# MCU_board_in_foot_v3.net
KiCad netlist of a schematic drawn in EAGLE
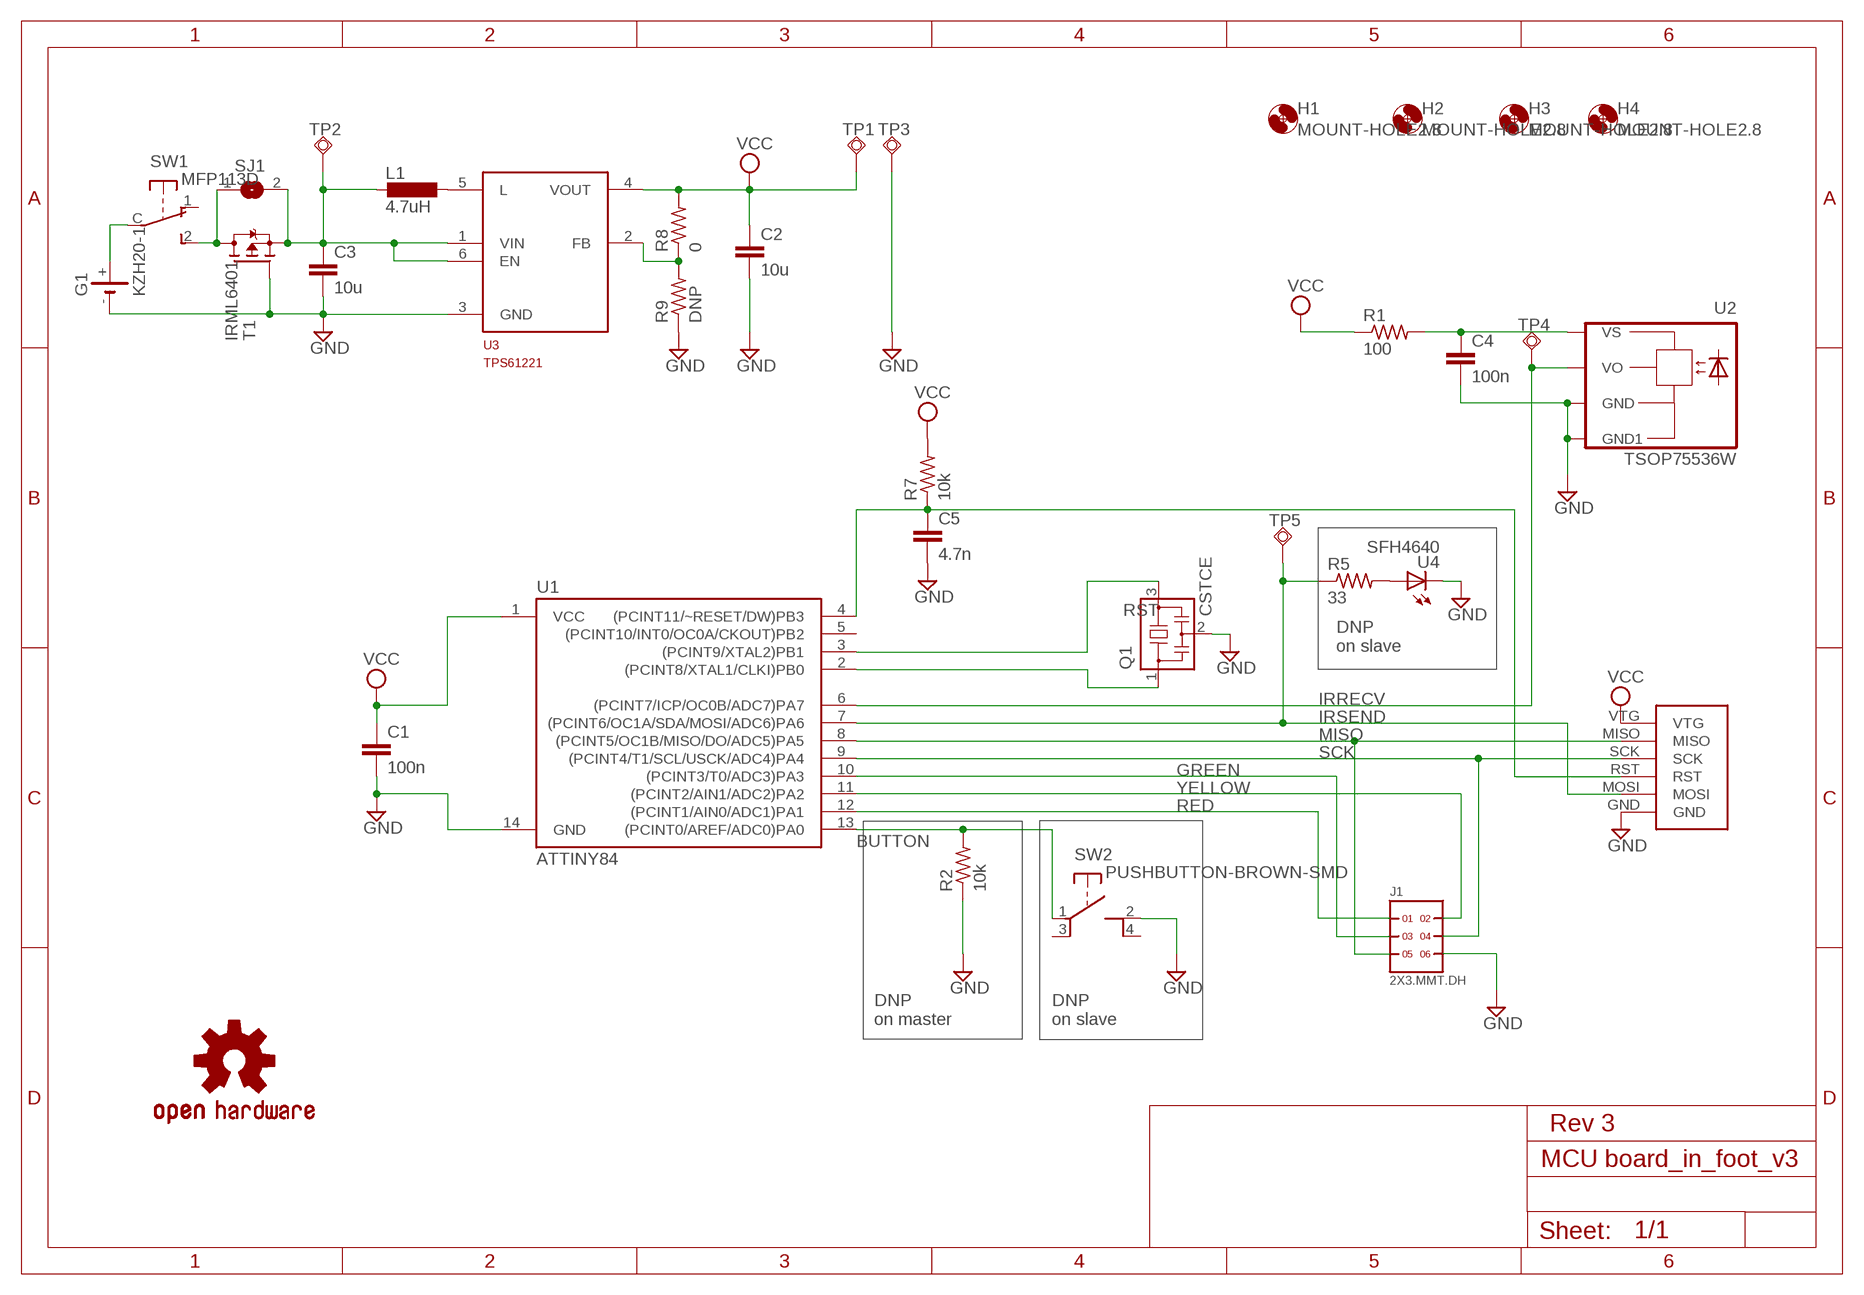
[diagram p0: schematic, sheet 1]

(export (version "E")
  (design (tool "Eeschema 10.0.6"))
  (components
    (comp (ref "C1")
      (value "100n")
      (footprint "eagle-import:0603-CAP")
      (libsource (lib "eagle-import") (part "CAP0603-CAP"))
    )
    (comp (ref "C2")
      (value "10u")
      (footprint "eagle-import:0603-CAP")
      (libsource (lib "eagle-import") (part "CAP0603-CAP"))
    )
    (comp (ref "C3")
      (value "10u")
      (footprint "eagle-import:0603-CAP")
      (libsource (lib "eagle-import") (part "MCU board_in_foot_99087_CAP0603-CAP"))
    )
    (comp (ref "C4")
      (value "100n")
      (footprint "eagle-import:0603-CAP")
      (libsource (lib "eagle-import") (part "CAP0603-CAP"))
    )
    (comp (ref "C5")
      (value "4.7n")
      (footprint "eagle-import:0603-CAP")
      (libsource (lib "eagle-import") (part "MCU board_in_foot_99087_CAP0603-CAP"))
    )
    (comp (ref "G1")
      (value "KZH20-1")
      (footprint "eagle-import:KZH20-1")
      (libsource (lib "eagle-import") (part "KZH20-1"))
    )
    (comp (ref "H1")
      (value "MOUNT-HOLE2.8")
      (footprint "eagle-import:2,8")
      (libsource (lib "eagle-import") (part "MCU board_in_foot_99087_MOUNT-HOLE2.8"))
    )
    (comp (ref "H2")
      (value "MOUNT-HOLE2.8")
      (footprint "eagle-import:2,8")
      (libsource (lib "eagle-import") (part "MOUNT-HOLE2.8"))
    )
    (comp (ref "H3")
      (value "MOUNT-HOLE2.8")
      (footprint "eagle-import:2,8")
      (libsource (lib "eagle-import") (part "MOUNT-HOLE2.8"))
    )
    (comp (ref "H4")
      (value "MOUNT-HOLE2.8")
      (footprint "eagle-import:2,8")
      (libsource (lib "eagle-import") (part "MCU board_in_foot_99087_MOUNT-HOLE2.8"))
    )
    (comp (ref "ISP")
      (value "ISP_POGOSURFACE")
      (footprint "eagle-import:ISP_SURFACE")
      (libsource (lib "eagle-import") (part "ISP_POGOSURFACE"))
    )
    (comp (ref "J1")
      (value "2X3.MMT.DH")
      (footprint "eagle-import:2X3_MMT.103.01.X.DH")
      (libsource (lib "eagle-import") (part "2X3.MMT.DH"))
    )
    (comp (ref "L1")
      (value "4.7uH")
      (footprint "eagle-import:EPL2010")
      (libsource (lib "eagle-import") (part "EPL2010"))
    )
    (comp (ref "LOGO1")
      (value "OSHW-LOGOS")
      (footprint "eagle-import:OSHW-LOGO-S")
      (libsource (lib "eagle-import") (part "OSHW-LOGOS"))
    )
    (comp (ref "Q1")
      (value "CSTCE")
      (footprint "eagle-import:CSTCE")
      (libsource (lib "eagle-import") (part "CSTCE"))
    )
    (comp (ref "R1")
      (value "100")
      (footprint "eagle-import:R0603")
      (libsource (lib "eagle-import") (part "R-US_R0603"))
    )
    (comp (ref "R2")
      (value "10k")
      (footprint "eagle-import:R0603")
      (libsource (lib "eagle-import") (part "R-US_R0603"))
    )
    (comp (ref "R5")
      (value "33")
      (footprint "eagle-import:R0603")
      (libsource (lib "eagle-import") (part "R-US_R0603"))
    )
    (comp (ref "R7")
      (value "10k")
      (footprint "eagle-import:R0603")
      (libsource (lib "eagle-import") (part "R-US_R0603"))
    )
    (comp (ref "R8")
      (value "0")
      (footprint "eagle-import:R0603")
      (libsource (lib "eagle-import") (part "R-US_R0603"))
    )
    (comp (ref "R9")
      (value "DNP")
      (footprint "eagle-import:R0603")
      (libsource (lib "eagle-import") (part "R-US_R0603"))
    )
    (comp (ref "SJ1") (value "SJ") (footprint "eagle-import:SJ") (libsource (lib "eagle-import") (part "SJ")))
    (comp (ref "SW1")
      (value "MFP113D")
      (footprint "eagle-import:MFP-SLIDER")
      (libsource (lib "eagle-import") (part "MFP113D"))
    )
    (comp (ref "SW2")
      (value "PUSHBUTTON-BROWN-SMD")
      (footprint "eagle-import:SMD-SW")
      (libsource (lib "eagle-import") (part "PUSHBUTTON-BROWN-SMD"))
    )
    (comp (ref "T1")
      (value "IRML6401")
      (footprint "eagle-import:SOT23")
      (libsource (lib "eagle-import") (part "IRML6401"))
    )
    (comp (ref "TP1")
      (value "TPSQTP20SQTH")
      (footprint "eagle-import:TP20SQTH")
      (libsource (lib "eagle-import") (part "TPSQTP20SQTH"))
    )
    (comp (ref "TP2")
      (value "TPSQTP20SQTH")
      (footprint "eagle-import:TP20SQTH")
      (libsource (lib "eagle-import") (part "TPSQTP20SQTH"))
    )
    (comp (ref "TP3")
      (value "TPSQTP20SQTH")
      (footprint "eagle-import:TP20SQTH")
      (libsource (lib "eagle-import") (part "TPSQTP20SQTH"))
    )
    (comp (ref "TP4")
      (value "TPSQTP20SQTH")
      (footprint "eagle-import:TP20SQTH")
      (libsource (lib "eagle-import") (part "TPSQTP20SQTH"))
    )
    (comp (ref "TP5")
      (value "TPSQTP20SQTH")
      (footprint "eagle-import:TP20SQTH")
      (libsource (lib "eagle-import") (part "TPSQTP20SQTH"))
    )
    (comp (ref "U1")
      (value "ATTINY84")
      (footprint "eagle-import:SO14")
      (libsource (lib "eagle-import") (part "ATTINY84"))
    )
    (comp (ref "U2")
      (value "TSOP75536W")
      (footprint "eagle-import:TSOP75W-TOPLOOK")
      (libsource (lib "eagle-import") (part "TSOP75WTOPLOOK"))
    )
    (comp (ref "U3")
      (value "TPS61221")
      (footprint "eagle-import:DCK-R_PDSO_G6")
      (libsource (lib "eagle-import") (part "TPS61220"))
    )
    (comp (ref "U4")
      (value "SFH4640")
      (footprint "eagle-import:MIDLED")
      (libsource (lib "eagle-import") (part "SFH4640"))
    )
  )
  (nets
    (net (code "1") (name "/BUTTON") (class "Default")
      (node (ref "R2") (pin "2") (pinfunction "2_2") (pintype "passive"))
      (node (ref "SW2") (pin "1") (pinfunction "P1_1") (pintype "passive"))
      (node (ref "U1") (pin "13") (pinfunction "(PCINT0/AREF/ADC0)PA0_13") (pintype "bidirectional"))
    )
    (net (code "2") (name "/GREEN") (class "Default")
      (node (ref "J1") (pin "3") (pinfunction "3_3") (pintype "bidirectional"))
      (node (ref "U1") (pin "10") (pinfunction "(PCINT3/T0/ADC3)PA3_10") (pintype "bidirectional"))
    )
    (net (code "3") (name "/IRRECV") (class "Default")
      (node (ref "TP4") (pin "TP") (pinfunction "TP_TP") (pintype "input"))
      (node (ref "U1") (pin "6") (pinfunction "(PCINT7/ICP/OC0B/ADC7)PA7_6") (pintype "bidirectional"))
      (node (ref "U2") (pin "3") (pinfunction "VO_3") (pintype "open_collector"))
    )
    (net (code "4") (name "/IRSEND") (class "Default")
      (node (ref "ISP") (pin "MOSI") (pinfunction "MOSI_MOSI") (pintype "bidirectional"))
      (node (ref "R5") (pin "1") (pinfunction "1_1") (pintype "passive"))
      (node (ref "TP5") (pin "TP") (pinfunction "TP_TP") (pintype "input"))
      (node (ref "U1") (pin "7") (pinfunction "(PCINT6/OC1A/SDA/MOSI/ADC6)PA6_7") (pintype "bidirectional"))
    )
    (net (code "5") (name "/MISO") (class "Default")
      (node (ref "ISP") (pin "MISO") (pinfunction "MISO_MISO") (pintype "bidirectional"))
      (node (ref "J1") (pin "5") (pinfunction "5_5") (pintype "bidirectional"))
      (node (ref "U1") (pin "8") (pinfunction "(PCINT5/OC1B/MISO/DO/ADC5)PA5_8") (pintype "bidirectional"))
    )
    (net (code "6") (name "/RED") (class "Default")
      (node (ref "J1") (pin "1") (pinfunction "1_1") (pintype "bidirectional"))
      (node (ref "U1") (pin "12") (pinfunction "(PCINT1/AIN0/ADC1)PA1_12") (pintype "bidirectional"))
    )
    (net (code "7") (name "/RST") (class "Default")
      (node (ref "C5") (pin "1") (pinfunction "1_1") (pintype "passive"))
      (node (ref "ISP") (pin "RST") (pinfunction "RST_RST") (pintype "bidirectional"))
      (node (ref "R7") (pin "1") (pinfunction "1_1") (pintype "passive"))
      (node (ref "U1") (pin "4") (pinfunction "(PCINT11/~{RESET/DW})PB3_4") (pintype "bidirectional"))
    )
    (net (code "8") (name "/SCK") (class "Default")
      (node (ref "ISP") (pin "SCK") (pinfunction "SCK_SCK") (pintype "bidirectional"))
      (node (ref "J1") (pin "4") (pinfunction "4_4") (pintype "bidirectional"))
      (node (ref "U1") (pin "9") (pinfunction "(PCINT4/T1/SCL/USCK/ADC4)PA4_9") (pintype "bidirectional"))
    )
    (net (code "9") (name "/YELLOW") (class "Default")
      (node (ref "J1") (pin "2") (pinfunction "2_2") (pintype "bidirectional"))
      (node (ref "U1") (pin "11") (pinfunction "(PCINT2/AIN1/ADC2)PA2_11") (pintype "bidirectional"))
    )
    (net (code "10") (name "GND") (class "Default")
      (node (ref "C1") (pin "2") (pinfunction "2_2") (pintype "passive"))
      (node (ref "C2") (pin "2") (pinfunction "2_2") (pintype "passive"))
      (node (ref "C3") (pin "2") (pinfunction "2_2") (pintype "passive"))
      (node (ref "C4") (pin "2") (pinfunction "2_2") (pintype "passive"))
      (node (ref "C5") (pin "2") (pinfunction "2_2") (pintype "passive"))
      (node (ref "G1") (pin "-") (pinfunction "-_-") (pintype "passive"))
      (node (ref "ISP") (pin "GND") (pinfunction "GND_GND") (pintype "bidirectional"))
      (node (ref "J1") (pin "6") (pinfunction "6_6") (pintype "bidirectional"))
      (node (ref "Q1") (pin "2") (pinfunction "2_2") (pintype "passive"))
      (node (ref "R2") (pin "1") (pinfunction "1_1") (pintype "passive"))
      (node (ref "R9") (pin "1") (pinfunction "1_1") (pintype "passive"))
      (node (ref "SW2") (pin "2") (pinfunction "S2_2") (pintype "passive"))
      (node (ref "T1") (pin "1") (pinfunction "G_1") (pintype "passive"))
      (node (ref "TP3") (pin "TP") (pinfunction "TP_TP") (pintype "input"))
      (node (ref "U1") (pin "14") (pinfunction "GND_14") (pintype "bidirectional"))
      (node (ref "U2") (pin "1") (pinfunction "GND_1") (pintype "power_in"))
      (node (ref "U2") (pin "4") (pinfunction "GND1_4") (pintype "power_in"))
      (node (ref "U3") (pin "3") (pinfunction "GND_3") (pintype "bidirectional"))
      (node (ref "U4") (pin "K") (pinfunction "C_K") (pintype "passive"))
    )
    (net (code "11") (name "Net-(L1-1)") (class "Default")
      (node (ref "C3") (pin "1") (pinfunction "1_1") (pintype "passive"))
      (node (ref "L1") (pin "P$1") (pinfunction "1_P$1") (pintype "passive"))
      (node (ref "SJ1") (pin "2") (pinfunction "2_2") (pintype "passive"))
      (node (ref "T1") (pin "2") (pinfunction "S_2") (pintype "passive"))
      (node (ref "TP2") (pin "TP") (pinfunction "TP_TP") (pintype "input"))
      (node (ref "U3") (pin "1") (pinfunction "VIN_1") (pintype "bidirectional"))
      (node (ref "U3") (pin "6") (pinfunction "EN_6") (pintype "bidirectional"))
    )
    (net (code "12") (name "Net-(L1-2)") (class "Default")
      (node (ref "L1") (pin "P$2") (pinfunction "2_P$2") (pintype "passive"))
      (node (ref "U3") (pin "5") (pinfunction "L_5") (pintype "bidirectional"))
    )
    (net (code "13") (name "Net-(R5-Pad2)") (class "Default")
      (node (ref "R5") (pin "2") (pinfunction "2_2") (pintype "passive"))
      (node (ref "U4") (pin "A") (pinfunction "A_A") (pintype "passive"))
    )
    (net (code "14") (name "Net-(SW1-P)") (class "Default")
      (node (ref "G1") (pin "+") (pinfunction "+_+") (pintype "passive"))
      (node (ref "SW1") (pin "C") (pinfunction "P_C") (pintype "passive"))
    )
    (net (code "15") (name "Net-(SW1-S)") (class "Default")
      (node (ref "SJ1") (pin "1") (pinfunction "1_1") (pintype "passive"))
      (node (ref "SW1") (pin "2") (pinfunction "S_2") (pintype "passive"))
      (node (ref "T1") (pin "3") (pinfunction "D_3") (pintype "passive"))
    )
    (net (code "16") (name "Net-(U1-(PCINT8{slash}XTAL1{slash}CLKI)PB0)") (class "Default")
      (node (ref "Q1") (pin "1") (pinfunction "1_1") (pintype "passive"))
      (node (ref "U1") (pin "2") (pinfunction "(PCINT8/XTAL1/CLKI)PB0_2") (pintype "bidirectional"))
    )
    (net (code "17") (name "Net-(U1-(PCINT9{slash}XTAL2)PB1)") (class "Default")
      (node (ref "Q1") (pin "3") (pinfunction "3_3") (pintype "passive"))
      (node (ref "U1") (pin "3") (pinfunction "(PCINT9/XTAL2)PB1_3") (pintype "bidirectional"))
    )
    (net (code "18") (name "Net-(U2-VS)") (class "Default")
      (node (ref "C4") (pin "1") (pinfunction "1_1") (pintype "passive"))
      (node (ref "R1") (pin "2") (pinfunction "2_2") (pintype "passive"))
      (node (ref "U2") (pin "2") (pinfunction "VS_2") (pintype "power_in"))
    )
    (net (code "19") (name "Net-(U3-FB)") (class "Default")
      (node (ref "R8") (pin "1") (pinfunction "1_1") (pintype "passive"))
      (node (ref "R9") (pin "2") (pinfunction "2_2") (pintype "passive"))
      (node (ref "U3") (pin "2") (pinfunction "FB_2") (pintype "bidirectional"))
    )
    (net (code "20") (name "VCC") (class "Default")
      (node (ref "C1") (pin "1") (pinfunction "1_1") (pintype "passive"))
      (node (ref "C2") (pin "1") (pinfunction "1_1") (pintype "passive"))
      (node (ref "ISP") (pin "VTG") (pinfunction "VTG_VTG") (pintype "bidirectional"))
      (node (ref "R1") (pin "1") (pinfunction "1_1") (pintype "passive"))
      (node (ref "R7") (pin "2") (pinfunction "2_2") (pintype "passive"))
      (node (ref "R8") (pin "2") (pinfunction "2_2") (pintype "passive"))
      (node (ref "TP1") (pin "TP") (pinfunction "TP_TP") (pintype "input"))
      (node (ref "U1") (pin "1") (pinfunction "VCC_1") (pintype "bidirectional"))
      (node (ref "U3") (pin "4") (pinfunction "VOUT_4") (pintype "bidirectional"))
    )
    (net (code "21") (name "unconnected-(SW1-O-Pad1)") (class "Default")
      (node (ref "SW1") (pin "1") (pinfunction "O_1") (pintype "passive"))
    )
    (net (code "22") (name "unconnected-(SW2-P3-Pad3)") (class "Default")
      (node (ref "SW2") (pin "3") (pinfunction "P3_3") (pintype "passive"))
    )
    (net (code "23") (name "unconnected-(SW2-S4-Pad4)") (class "Default")
      (node (ref "SW2") (pin "4") (pinfunction "S4_4") (pintype "passive"))
    )
    (net (code "24") (name "unconnected-(U1-(PCINT10{slash}INT0{slash}OC0A{slash}CKOUT)PB2-Pad5)") (class "Default")
      (node (ref "U1") (pin "5") (pinfunction "(PCINT10/INT0/OC0A/CKOUT)PB2_5") (pintype "bidirectional"))
    )
  )
)
